# ProTrinket_HPdisplay.net
KiCad netlist of a schematic drawn in EAGLE
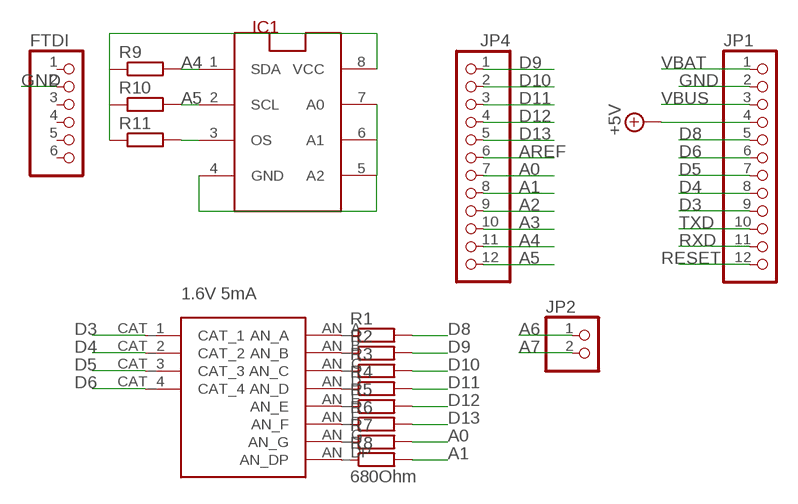
[diagram p0: schematic, sheet 1]

(export (version "E")
  (design (tool "Eeschema 10.0.6"))
  (components
    (comp (ref "FTDI")
      (value "PINHD-1X6CB")
      (footprint "eagle-import:1X06-CLEANBIG")
      (libsource (lib "eagle-import") (part "PINHD-1X6CB"))
    )
    (comp (ref "IC1")
      (value "LM75_ICN")
      (footprint "eagle-import:SO8_LM75")
      (libsource (lib "eagle-import") (part "LM75_ICN"))
    )
    (comp (ref "JP1")
      (value "PINHD-1X12-CB")
      (footprint "eagle-import:1X12-CB")
      (libsource (lib "eagle-import") (part "PINHD-1X12-CB"))
    )
    (comp (ref "JP2")
      (value "HEADER-1X2ROUND")
      (footprint "eagle-import:1X02_ROUND")
      (libsource (lib "eagle-import") (part "HEADER-1X2ROUND"))
    )
    (comp (ref "JP4")
      (value "PINHD-1X12-CB")
      (footprint "eagle-import:1X12-CB")
      (libsource (lib "eagle-import") (part "PINHD-1X12-CB"))
    )
    (comp (ref "R1")
      (value "R-EU_R1206")
      (footprint "eagle-import:R1206")
      (libsource (lib "eagle-import") (part "R-EU_R1206"))
    )
    (comp (ref "R2")
      (value "R-EU_R1206")
      (footprint "eagle-import:R1206")
      (libsource (lib "eagle-import") (part "R-EU_R1206"))
    )
    (comp (ref "R3")
      (value "R-EU_R1206")
      (footprint "eagle-import:R1206")
      (libsource (lib "eagle-import") (part "R-EU_R1206"))
    )
    (comp (ref "R4")
      (value "R-EU_R1206")
      (footprint "eagle-import:R1206")
      (libsource (lib "eagle-import") (part "R-EU_R1206"))
    )
    (comp (ref "R5")
      (value "R-EU_R1206")
      (footprint "eagle-import:R1206")
      (libsource (lib "eagle-import") (part "R-EU_R1206"))
    )
    (comp (ref "R6")
      (value "R-EU_R1206")
      (footprint "eagle-import:R1206")
      (libsource (lib "eagle-import") (part "R-EU_R1206"))
    )
    (comp (ref "R7")
      (value "R-EU_R1206")
      (footprint "eagle-import:R1206")
      (libsource (lib "eagle-import") (part "R-EU_R1206"))
    )
    (comp (ref "R8")
      (value "680Ohm")
      (footprint "eagle-import:R1206")
      (libsource (lib "eagle-import") (part "R-EU_R1206"))
    )
    (comp (ref "R9")
      (value "R-EU_R0603")
      (footprint "eagle-import:R0603")
      (libsource (lib "eagle-import") (part "resistor_R-EU_R0603"))
    )
    (comp (ref "R10")
      (value "R-EU_R0603")
      (footprint "eagle-import:R0603")
      (libsource (lib "eagle-import") (part "resistor_R-EU_R0603"))
    )
    (comp (ref "R11")
      (value "R-EU_R0603")
      (footprint "eagle-import:R0603")
      (libsource (lib "eagle-import") (part "resistor_R-EU_R0603"))
    )
    (comp (ref "U$1")
      (value "QDSP-6064")
      (footprint "eagle-import:QDSP-6064")
      (libsource (lib "eagle-import") (part "QDSP-6064"))
    )
  )
  (nets
    (net (code "1") (name "+5V") (class "Default")
      (node (ref "IC1") (pin "8") (pinfunction "VCC_8") (pintype "power_in"))
      (node (ref "JP1") (pin "4") (pinfunction "4_4") (pintype "passive"))
      (node (ref "R10") (pin "1") (pinfunction "1_1") (pintype "passive"))
      (node (ref "R11") (pin "1") (pinfunction "1_1") (pintype "passive"))
      (node (ref "R9") (pin "1") (pinfunction "1_1") (pintype "passive"))
    )
    (net (code "2") (name "/A0") (class "Default")
      (node (ref "JP4") (pin "7") (pinfunction "7_7") (pintype "passive"))
      (node (ref "R7") (pin "2") (pinfunction "2_2") (pintype "passive"))
    )
    (net (code "3") (name "/A1") (class "Default")
      (node (ref "JP4") (pin "8") (pinfunction "8_8") (pintype "passive"))
      (node (ref "R8") (pin "2") (pinfunction "2_2") (pintype "passive"))
    )
    (net (code "4") (name "/A2") (class "Default")
      (node (ref "JP4") (pin "9") (pinfunction "9_9") (pintype "passive"))
    )
    (net (code "5") (name "/A3") (class "Default")
      (node (ref "JP4") (pin "10") (pinfunction "10_10") (pintype "passive"))
    )
    (net (code "6") (name "/A4") (class "Default")
      (node (ref "IC1") (pin "1") (pinfunction "SDA_1") (pintype "bidirectional"))
      (node (ref "JP4") (pin "11") (pinfunction "11_11") (pintype "passive"))
      (node (ref "R9") (pin "2") (pinfunction "2_2") (pintype "passive"))
    )
    (net (code "7") (name "/A5") (class "Default")
      (node (ref "IC1") (pin "2") (pinfunction "SCL_2") (pintype "bidirectional"))
      (node (ref "JP4") (pin "12") (pinfunction "12_12") (pintype "passive"))
      (node (ref "R10") (pin "2") (pinfunction "2_2") (pintype "passive"))
    )
    (net (code "8") (name "/A6") (class "Default")
      (node (ref "JP2") (pin "1") (pinfunction "1_1") (pintype "passive"))
    )
    (net (code "9") (name "/A7") (class "Default")
      (node (ref "JP2") (pin "2") (pinfunction "2_2") (pintype "passive"))
    )
    (net (code "10") (name "/AREF") (class "Default")
      (node (ref "JP4") (pin "6") (pinfunction "6_6") (pintype "passive"))
    )
    (net (code "11") (name "/D3") (class "Default")
      (node (ref "JP1") (pin "9") (pinfunction "9_9") (pintype "passive"))
      (node (ref "U$1") (pin "CAT_1") (pinfunction "CAT_1_CAT_1") (pintype "bidirectional"))
    )
    (net (code "12") (name "/D4") (class "Default")
      (node (ref "JP1") (pin "8") (pinfunction "8_8") (pintype "passive"))
      (node (ref "U$1") (pin "CAT_2") (pinfunction "CAT_2_CAT_2") (pintype "bidirectional"))
    )
    (net (code "13") (name "/D5") (class "Default")
      (node (ref "JP1") (pin "7") (pinfunction "7_7") (pintype "passive"))
      (node (ref "U$1") (pin "CAT_3") (pinfunction "CAT_3_CAT_3") (pintype "bidirectional"))
    )
    (net (code "14") (name "/D6") (class "Default")
      (node (ref "JP1") (pin "6") (pinfunction "6_6") (pintype "passive"))
      (node (ref "U$1") (pin "CAT_4") (pinfunction "CAT_4_CAT_4") (pintype "bidirectional"))
    )
    (net (code "15") (name "/D8") (class "Default")
      (node (ref "JP1") (pin "5") (pinfunction "5_5") (pintype "passive"))
      (node (ref "R1") (pin "2") (pinfunction "2_2") (pintype "passive"))
    )
    (net (code "16") (name "/D9") (class "Default")
      (node (ref "JP4") (pin "1") (pinfunction "1_1") (pintype "passive"))
      (node (ref "R2") (pin "2") (pinfunction "2_2") (pintype "passive"))
    )
    (net (code "17") (name "/D10") (class "Default")
      (node (ref "JP4") (pin "2") (pinfunction "2_2") (pintype "passive"))
      (node (ref "R3") (pin "2") (pinfunction "2_2") (pintype "passive"))
    )
    (net (code "18") (name "/D11") (class "Default")
      (node (ref "JP4") (pin "3") (pinfunction "3_3") (pintype "passive"))
      (node (ref "R4") (pin "2") (pinfunction "2_2") (pintype "passive"))
    )
    (net (code "19") (name "/D12") (class "Default")
      (node (ref "JP4") (pin "4") (pinfunction "4_4") (pintype "passive"))
      (node (ref "R5") (pin "2") (pinfunction "2_2") (pintype "passive"))
    )
    (net (code "20") (name "/D13") (class "Default")
      (node (ref "JP4") (pin "5") (pinfunction "5_5") (pintype "passive"))
      (node (ref "R6") (pin "2") (pinfunction "2_2") (pintype "passive"))
    )
    (net (code "21") (name "/GND") (class "Default")
      (node (ref "FTDI") (pin "2") (pinfunction "2_2") (pintype "passive"))
      (node (ref "IC1") (pin "4") (pinfunction "GND_4") (pintype "power_in"))
      (node (ref "IC1") (pin "5") (pinfunction "A2_5") (pintype "input"))
      (node (ref "IC1") (pin "6") (pinfunction "A1_6") (pintype "input"))
      (node (ref "IC1") (pin "7") (pinfunction "A0_7") (pintype "input"))
      (node (ref "JP1") (pin "2") (pinfunction "2_2") (pintype "passive"))
    )
    (net (code "22") (name "/RESET") (class "Default")
      (node (ref "JP1") (pin "12") (pinfunction "12_12") (pintype "passive"))
    )
    (net (code "23") (name "/RXD") (class "Default")
      (node (ref "JP1") (pin "11") (pinfunction "11_11") (pintype "passive"))
    )
    (net (code "24") (name "/TXD") (class "Default")
      (node (ref "JP1") (pin "10") (pinfunction "10_10") (pintype "passive"))
    )
    (net (code "25") (name "/VBAT") (class "Default")
      (node (ref "JP1") (pin "1") (pinfunction "1_1") (pintype "passive"))
    )
    (net (code "26") (name "/VBUS") (class "Default")
      (node (ref "JP1") (pin "3") (pinfunction "3_3") (pintype "passive"))
    )
    (net (code "27") (name "Net-(IC1-OS)") (class "Default")
      (node (ref "IC1") (pin "3") (pinfunction "OS_3") (pintype "output"))
      (node (ref "R11") (pin "2") (pinfunction "2_2") (pintype "passive"))
    )
    (net (code "28") (name "Net-(R1-Pad1)") (class "Default")
      (node (ref "R1") (pin "1") (pinfunction "1_1") (pintype "passive"))
      (node (ref "U$1") (pin "AN_A") (pinfunction "AN_A_AN_A") (pintype "bidirectional"))
    )
    (net (code "29") (name "Net-(R2-Pad1)") (class "Default")
      (node (ref "R2") (pin "1") (pinfunction "1_1") (pintype "passive"))
      (node (ref "U$1") (pin "AN_B") (pinfunction "AN_B_AN_B") (pintype "bidirectional"))
    )
    (net (code "30") (name "Net-(R3-Pad1)") (class "Default")
      (node (ref "R3") (pin "1") (pinfunction "1_1") (pintype "passive"))
      (node (ref "U$1") (pin "AN_C") (pinfunction "AN_C_AN_C") (pintype "bidirectional"))
    )
    (net (code "31") (name "Net-(R4-Pad1)") (class "Default")
      (node (ref "R4") (pin "1") (pinfunction "1_1") (pintype "passive"))
      (node (ref "U$1") (pin "AN_D") (pinfunction "AN_D_AN_D") (pintype "bidirectional"))
    )
    (net (code "32") (name "Net-(R5-Pad1)") (class "Default")
      (node (ref "R5") (pin "1") (pinfunction "1_1") (pintype "passive"))
      (node (ref "U$1") (pin "AN_E") (pinfunction "AN_E_AN_E") (pintype "bidirectional"))
    )
    (net (code "33") (name "Net-(R6-Pad1)") (class "Default")
      (node (ref "R6") (pin "1") (pinfunction "1_1") (pintype "passive"))
      (node (ref "U$1") (pin "AN_F") (pinfunction "AN_F_AN_F") (pintype "bidirectional"))
    )
    (net (code "34") (name "Net-(R7-Pad1)") (class "Default")
      (node (ref "R7") (pin "1") (pinfunction "1_1") (pintype "passive"))
      (node (ref "U$1") (pin "AN_G") (pinfunction "AN_G_AN_G") (pintype "bidirectional"))
    )
    (net (code "35") (name "Net-(R8-Pad1)") (class "Default")
      (node (ref "R8") (pin "1") (pinfunction "1_1") (pintype "passive"))
      (node (ref "U$1") (pin "AN_DP") (pinfunction "AN_DP_AN_DP") (pintype "bidirectional"))
    )
    (net (code "36") (name "unconnected-(FTDI-Pad1)") (class "Default")
      (node (ref "FTDI") (pin "1") (pinfunction "1_1") (pintype "passive"))
    )
    (net (code "37") (name "unconnected-(FTDI-Pad3)") (class "Default")
      (node (ref "FTDI") (pin "3") (pinfunction "3_3") (pintype "passive"))
    )
    (net (code "38") (name "unconnected-(FTDI-Pad4)") (class "Default")
      (node (ref "FTDI") (pin "4") (pinfunction "4_4") (pintype "passive"))
    )
    (net (code "39") (name "unconnected-(FTDI-Pad5)") (class "Default")
      (node (ref "FTDI") (pin "5") (pinfunction "5_5") (pintype "passive"))
    )
    (net (code "40") (name "unconnected-(FTDI-Pad6)") (class "Default")
      (node (ref "FTDI") (pin "6") (pinfunction "6_6") (pintype "passive"))
    )
  )
)
